# FPC-isoIOs-Power_Protection_AP22653.net
KiCad netlist of a schematic drawn in Altium Designer
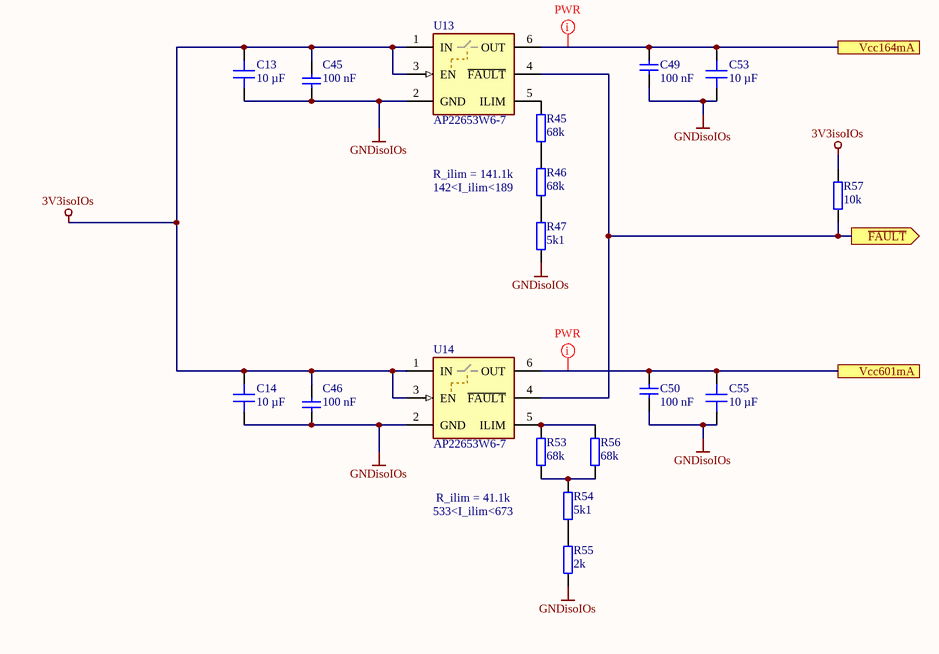
[diagram p0: FPC-isoIOs-Power_Protection_AP22653.SchDoc]

(export (version "E")
  (design (tool "Eeschema 10.0.6"))
  (components
    (comp (ref "C13")
      (value "10 µF")
      (footprint "C_0603_TE")
      (description "Capacitor 0603, 16 VDC, 10 µF, X5R")
      (fields
        (field (name "MANUFACTURER PART NUMBER") "CL10A106MO8NQNC")
        (field (name "MANUFACTURER") "Samsung Electro-Mechanics")
        (field (name "CREATED FROM") "AGeiger")
      )
      (libsource (lib "user") (part "Capacitor"))
    )
    (comp (ref "C14")
      (value "10 µF")
      (footprint "C_0603_TE")
      (description "Capacitor 0603, 16 VDC, 10 µF, X5R")
      (fields
        (field (name "MANUFACTURER PART NUMBER") "CL10A106MO8NQNC")
        (field (name "MANUFACTURER") "Samsung Electro-Mechanics")
        (field (name "CREATED FROM") "AGeiger")
      )
      (libsource (lib "user") (part "Capacitor"))
    )
    (comp (ref "C45")
      (value "100 nF")
      (footprint "C_0603_TE")
      (description "Generic capacitor")
      (fields
        (field (name "MANUFACTURER PART NUMBER") "UZgen_C_0603_100nF_50V_X7R")
        (field (name "MANUFACTURER") "UZgen")
        (field (name "CREATED FROM") "AGeiger")
      )
      (libsource (lib "user") (part "CAP-NP"))
    )
    (comp (ref "C46")
      (value "100 nF")
      (footprint "C_0603_TE")
      (description "Generic capacitor")
      (fields
        (field (name "MANUFACTURER PART NUMBER") "UZgen_C_0603_100nF_50V_X7R")
        (field (name "MANUFACTURER") "UZgen")
        (field (name "CREATED FROM") "AGeiger")
      )
      (libsource (lib "user") (part "CAP-NP"))
    )
    (comp (ref "C49")
      (value "100 nF")
      (footprint "C_0603_TE")
      (description "Generic capacitor")
      (fields
        (field (name "MANUFACTURER PART NUMBER") "UZgen_C_0603_100nF_50V_X7R")
        (field (name "MANUFACTURER") "UZgen")
        (field (name "CREATED FROM") "AGeiger")
      )
      (libsource (lib "user") (part "CAP-NP"))
    )
    (comp (ref "C50")
      (value "100 nF")
      (footprint "C_0603_TE")
      (description "Generic capacitor")
      (fields
        (field (name "MANUFACTURER PART NUMBER") "UZgen_C_0603_100nF_50V_X7R")
        (field (name "MANUFACTURER") "UZgen")
        (field (name "CREATED FROM") "AGeiger")
      )
      (libsource (lib "user") (part "CAP-NP"))
    )
    (comp (ref "C53")
      (value "10 µF")
      (footprint "C_0603_TE")
      (description "Capacitor 0603, 16 VDC, 10 µF, X5R")
      (fields
        (field (name "MANUFACTURER PART NUMBER") "CL10A106MO8NQNC")
        (field (name "MANUFACTURER") "Samsung Electro-Mechanics")
        (field (name "CREATED FROM") "AGeiger")
      )
      (libsource (lib "user") (part "Capacitor"))
    )
    (comp (ref "C55")
      (value "10 µF")
      (footprint "C_0603_TE")
      (description "Capacitor 0603, 16 VDC, 10 µF, X5R")
      (fields
        (field (name "MANUFACTURER PART NUMBER") "CL10A106MO8NQNC")
        (field (name "MANUFACTURER") "Samsung Electro-Mechanics")
        (field (name "CREATED FROM") "AGeiger")
      )
      (libsource (lib "user") (part "Capacitor"))
    )
    (comp (ref "R45")
      (value "68k")
      (footprint "R_0603_TE")
      (description "Generic resistor")
      (fields
        (field (name "MANUFACTURER PART NUMBER") "UZgen_R_0603_68k")
        (field (name "MANUFACTURER") "UZgen")
        (field (name "CREATED FROM") "UZgenTool")
      )
      (libsource (lib "user") (part "RES"))
    )
    (comp (ref "R46")
      (value "68k")
      (footprint "R_0603_TE")
      (description "Generic resistor")
      (fields
        (field (name "MANUFACTURER PART NUMBER") "UZgen_R_0603_68k")
        (field (name "MANUFACTURER") "UZgen")
        (field (name "CREATED FROM") "UZgenTool")
      )
      (libsource (lib "user") (part "RES"))
    )
    (comp (ref "R47")
      (value "5k1")
      (footprint "R_0603_TE")
      (description "Generic resistor")
      (fields
        (field (name "MANUFACTURER PART NUMBER") "UZgen_R_0603_5k1")
        (field (name "MANUFACTURER") "UZgen")
        (field (name "CREATED FROM") "UZgenTool")
      )
      (libsource (lib "user") (part "RES"))
    )
    (comp (ref "R53")
      (value "68k")
      (footprint "R_0603_TE")
      (description "Generic resistor")
      (fields
        (field (name "MANUFACTURER PART NUMBER") "UZgen_R_0603_68k")
        (field (name "MANUFACTURER") "UZgen")
        (field (name "CREATED FROM") "UZgenTool")
      )
      (libsource (lib "user") (part "RES"))
    )
    (comp (ref "R54")
      (value "5k1")
      (footprint "R_0603_TE")
      (description "Generic resistor")
      (fields
        (field (name "MANUFACTURER PART NUMBER") "UZgen_R_0603_5k1")
        (field (name "MANUFACTURER") "UZgen")
        (field (name "CREATED FROM") "UZgenTool")
      )
      (libsource (lib "user") (part "RES"))
    )
    (comp (ref "R55")
      (value "2k")
      (footprint "R_0603_TE")
      (description "Generic resistor")
      (fields
        (field (name "MANUFACTURER PART NUMBER") "UZgen_R_0603_2k")
        (field (name "MANUFACTURER") "UZgen")
        (field (name "CREATED FROM") "UZgenTool")
      )
      (libsource (lib "user") (part "RES"))
    )
    (comp (ref "R56")
      (value "68k")
      (footprint "R_0603_TE")
      (description "Generic resistor")
      (fields
        (field (name "MANUFACTURER PART NUMBER") "UZgen_R_0603_68k")
        (field (name "MANUFACTURER") "UZgen")
        (field (name "CREATED FROM") "UZgenTool")
      )
      (libsource (lib "user") (part "RES"))
    )
    (comp (ref "R57")
      (value "10k")
      (footprint "R_0603_TE")
      (description "Generic resistor")
      (fields
        (field (name "MANUFACTURER PART NUMBER") "UZgen_R_0603_10k")
        (field (name "MANUFACTURER") "UZgen")
        (field (name "CREATED FROM") "AGeiger")
      )
      (libsource (lib "user") (part "RES"))
    )
    (comp (ref "U13")
      (value "AP22653W6-7")
      (footprint "TSOT26-6")
      (description "Precision Adjustable Current-limited Power Switch")
      (fields
        (field (name "MANUFACTURER") "Diodes Incorporated")
        (field (name "LCSC PART NUMBER") "C2158037")
        (field (name "CREATED FROM") "MGeier")
      )
      (libsource (lib "user") (part "AP22653W6-7"))
    )
    (comp (ref "U14")
      (value "AP22653W6-7")
      (footprint "TSOT26-6")
      (description "Precision Adjustable Current-limited Power Switch")
      (fields
        (field (name "MANUFACTURER") "Diodes Incorporated")
        (field (name "LCSC PART NUMBER") "C2158037")
        (field (name "CREATED FROM") "MGeier")
      )
      (libsource (lib "user") (part "AP22653W6-7"))
    )
  )
  (nets
    (net (code "1") (name "/Vcc164mA") (class "Default")
      (node (ref "C49") (pin "1") (pinfunction "1_1") (pintype "passive"))
      (node (ref "C53") (pin "2") (pinfunction "2_2") (pintype "passive"))
      (node (ref "U13") (pin "6") (pinfunction "OUT_6") (pintype "power_in"))
    )
    (net (code "2") (name "/Vcc601mA") (class "Default")
      (node (ref "C50") (pin "1") (pinfunction "1_1") (pintype "passive"))
      (node (ref "C55") (pin "2") (pinfunction "2_2") (pintype "passive"))
      (node (ref "U14") (pin "6") (pinfunction "OUT_6") (pintype "power_in"))
    )
    (net (code "3") (name "/~{FAULT}") (class "Default")
      (node (ref "R57") (pin "1") (pinfunction "1_1") (pintype "passive"))
      (node (ref "U13") (pin "4") (pinfunction "~{FAULT}_4") (pintype "open_collector"))
      (node (ref "U14") (pin "4") (pinfunction "~{FAULT}_4") (pintype "open_collector"))
    )
    (net (code "4") (name "3V3isoIOs") (class "Default")
      (node (ref "C13") (pin "2") (pinfunction "2_2") (pintype "passive"))
      (node (ref "C14") (pin "2") (pinfunction "2_2") (pintype "passive"))
      (node (ref "C45") (pin "1") (pinfunction "1_1") (pintype "passive"))
      (node (ref "C46") (pin "1") (pinfunction "1_1") (pintype "passive"))
      (node (ref "R57") (pin "2") (pinfunction "2_2") (pintype "passive"))
      (node (ref "U13") (pin "1") (pinfunction "IN_1") (pintype "power_in"))
      (node (ref "U13") (pin "3") (pinfunction "EN_3") (pintype "input"))
      (node (ref "U14") (pin "1") (pinfunction "IN_1") (pintype "power_in"))
      (node (ref "U14") (pin "3") (pinfunction "EN_3") (pintype "input"))
    )
    (net (code "5") (name "GNDisoIOs") (class "Default")
      (node (ref "C13") (pin "1") (pinfunction "1_1") (pintype "passive"))
      (node (ref "C14") (pin "1") (pinfunction "1_1") (pintype "passive"))
      (node (ref "C45") (pin "2") (pinfunction "2_2") (pintype "passive"))
      (node (ref "C46") (pin "2") (pinfunction "2_2") (pintype "passive"))
      (node (ref "C49") (pin "2") (pinfunction "2_2") (pintype "passive"))
      (node (ref "C50") (pin "2") (pinfunction "2_2") (pintype "passive"))
      (node (ref "C53") (pin "1") (pinfunction "1_1") (pintype "passive"))
      (node (ref "C55") (pin "1") (pinfunction "1_1") (pintype "passive"))
      (node (ref "R47") (pin "1") (pinfunction "1_1") (pintype "passive"))
      (node (ref "R55") (pin "1") (pinfunction "1_1") (pintype "passive"))
      (node (ref "U13") (pin "2") (pinfunction "GND_2") (pintype "power_in"))
      (node (ref "U14") (pin "2") (pinfunction "GND_2") (pintype "power_in"))
    )
    (net (code "6") (name "Net-(R45-Pad1)") (class "Default")
      (node (ref "R45") (pin "1") (pinfunction "1_1") (pintype "passive"))
      (node (ref "R46") (pin "2") (pinfunction "2_2") (pintype "passive"))
    )
    (net (code "7") (name "Net-(R46-Pad1)") (class "Default")
      (node (ref "R46") (pin "1") (pinfunction "1_1") (pintype "passive"))
      (node (ref "R47") (pin "2") (pinfunction "2_2") (pintype "passive"))
    )
    (net (code "8") (name "Net-(R53-Pad1)") (class "Default")
      (node (ref "R53") (pin "1") (pinfunction "1_1") (pintype "passive"))
      (node (ref "R54") (pin "2") (pinfunction "2_2") (pintype "passive"))
      (node (ref "R56") (pin "1") (pinfunction "1_1") (pintype "passive"))
    )
    (net (code "9") (name "Net-(R54-Pad1)") (class "Default")
      (node (ref "R54") (pin "1") (pinfunction "1_1") (pintype "passive"))
      (node (ref "R55") (pin "2") (pinfunction "2_2") (pintype "passive"))
    )
    (net (code "10") (name "Net-(U13-ILIM)") (class "Default")
      (node (ref "R45") (pin "2") (pinfunction "2_2") (pintype "passive"))
      (node (ref "U13") (pin "5") (pinfunction "ILIM_5") (pintype "passive"))
    )
    (net (code "11") (name "Net-(U14-ILIM)") (class "Default")
      (node (ref "R53") (pin "2") (pinfunction "2_2") (pintype "passive"))
      (node (ref "R56") (pin "2") (pinfunction "2_2") (pintype "passive"))
      (node (ref "U14") (pin "5") (pinfunction "ILIM_5") (pintype "passive"))
    )
  )
)
